# Control.net
KiCad netlist of a schematic drawn in Altium Designer
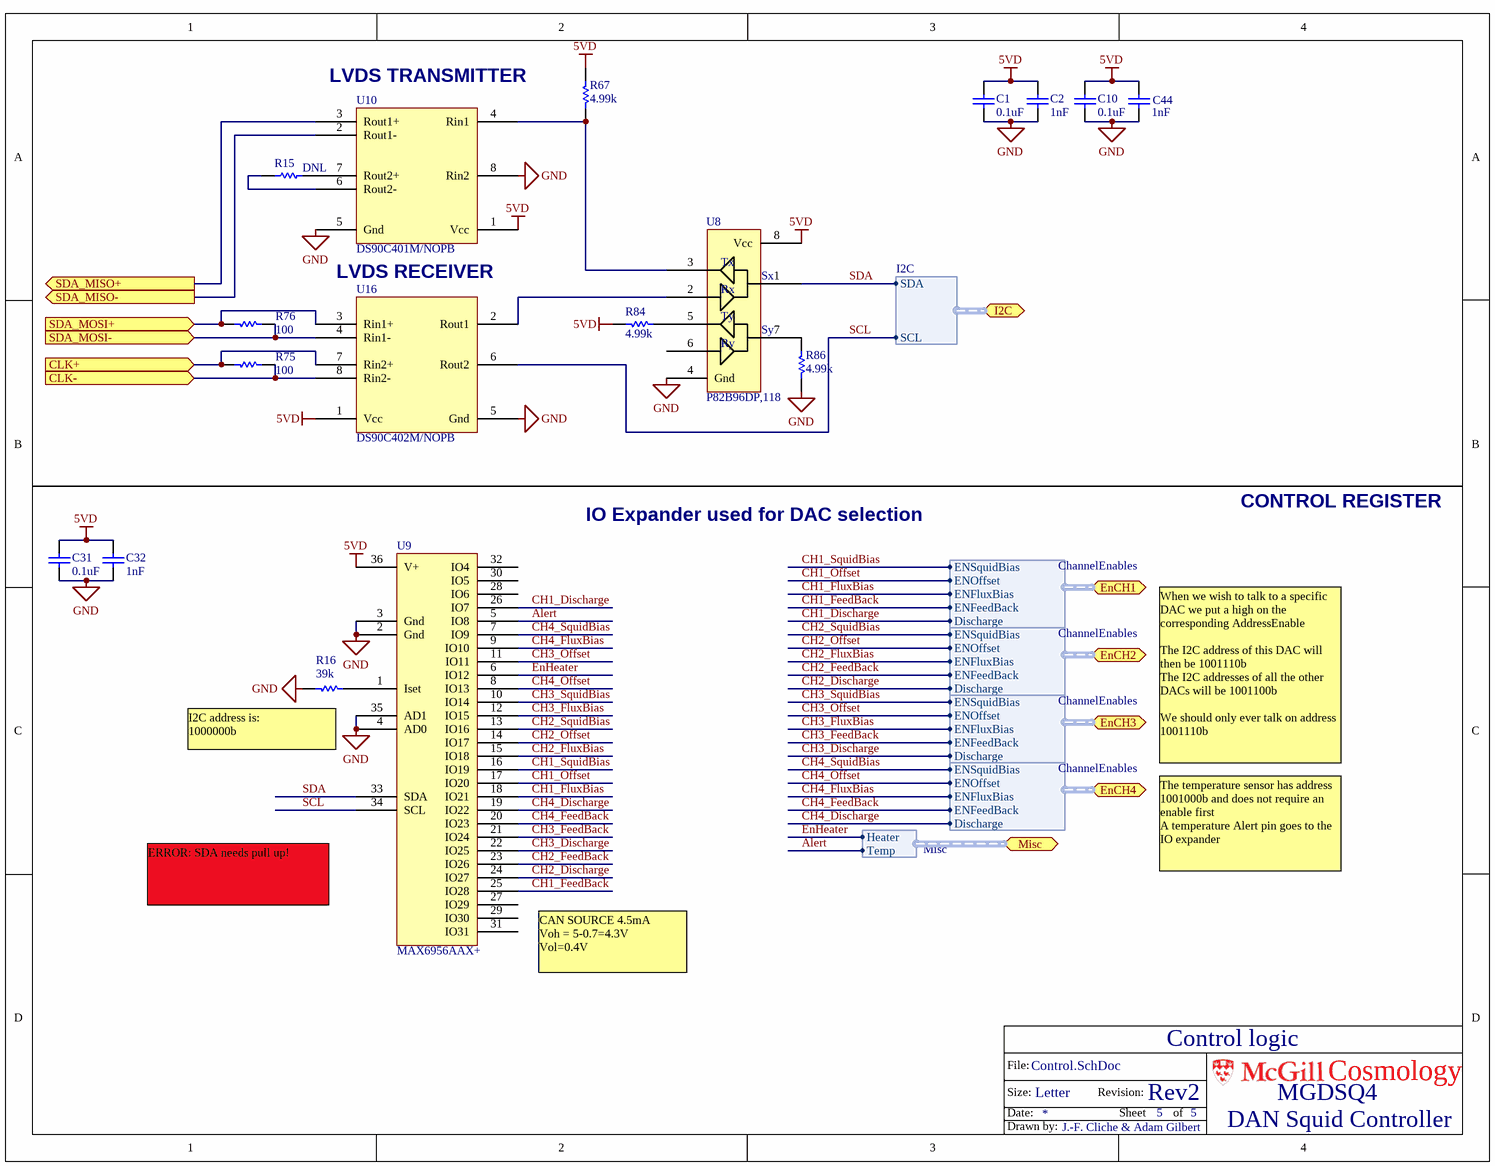
[diagram p0: Control.SchDoc]

(export (version "E")
  (design (tool "Eeschema 10.0.6"))
  (components
    (comp (ref "C1")
      (value "0.1uF")
      (footprint "0603")
      (description "Capacitor, Ceramic, 0603")
      (fields (field (name "MANUFACTURER") "Generic"))
      (libsource (lib "MiniSquidCtrl") (part "Cap0603"))
    )
    (comp (ref "C2")
      (value "1nF")
      (footprint "0603")
      (description "Capacitor, Ceramic, 0603")
      (fields (field (name "MANUFACTURER") "Generic"))
      (libsource (lib "MiniSquidCtrl") (part "Cap0603"))
    )
    (comp (ref "C10")
      (value "0.1uF")
      (footprint "0603")
      (description "Capacitor, Ceramic, 0603")
      (fields (field (name "MANUFACTURER") "Generic"))
      (libsource (lib "MiniSquidCtrl") (part "Cap0603"))
    )
    (comp (ref "C31")
      (value "0.1uF")
      (footprint "0603")
      (description "Capacitor, Ceramic, 0603")
      (fields (field (name "MANUFACTURER") "Generic"))
      (libsource (lib "MiniSquidCtrl") (part "Cap0603"))
    )
    (comp (ref "C32")
      (value "1nF")
      (footprint "0603")
      (description "Capacitor, Ceramic, 0603")
      (fields (field (name "MANUFACTURER") "Generic"))
      (libsource (lib "MiniSquidCtrl") (part "Cap0603"))
    )
    (comp (ref "C44")
      (value "1nF")
      (footprint "0603")
      (description "Capacitor, Ceramic, 0603")
      (fields (field (name "MANUFACTURER") "Generic"))
      (libsource (lib "MiniSquidCtrl") (part "Cap0603"))
    )
    (comp (ref "R15")
      (value "DNL")
      (footprint "0603")
      (description "RES 0603")
      (fields (field (name "MANUFACTURER") "Generic"))
      (libsource (lib "MiniSquidCtrl") (part "Res0603"))
    )
    (comp (ref "R16")
      (value "39k")
      (description "RES 0603")
      (fields (field (name "MANUFACTURER") "Generic") (field (name "TOLERANCE") "±1%"))
      (libsource (lib "MiniSquidCtrl") (part "RES 0603"))
    )
    (comp (ref "R67")
      (value "4.99k")
      (footprint "0603")
      (description "RES 0603")
      (fields (field (name "MANUFACTURER") "Generic"))
      (libsource (lib "MiniSquidCtrl") (part "Res0603"))
    )
    (comp (ref "R75")
      (value "100")
      (footprint "0603")
      (description "RES 0603")
      (fields (field (name "MANUFACTURER") "Generic"))
      (libsource (lib "MiniSquidCtrl") (part "RES 0603"))
    )
    (comp (ref "R76")
      (value "100")
      (footprint "0603")
      (description "RES 0603")
      (fields (field (name "MANUFACTURER") "Generic"))
      (libsource (lib "MiniSquidCtrl") (part "RES 0603"))
    )
    (comp (ref "R84")
      (value "4.99k")
      (footprint "0603")
      (description "RES 0603")
      (fields (field (name "MANUFACTURER") "Generic"))
      (libsource (lib "MiniSquidCtrl") (part "Res0603"))
    )
    (comp (ref "R86")
      (value "4.99k")
      (footprint "0603")
      (description "RES 0603")
      (fields (field (name "MANUFACTURER") "Generic"))
      (libsource (lib "MiniSquidCtrl") (part "Res0603"))
    )
    (comp (ref "U8")
      (value "P82B96DP,118")
      (footprint "MSOP8-P82B96")
      (description "IC DUAL BI-DIR BUS BUFFER 8-TSSOP")
      (libsource (lib "MiniSquidCtrl") (part "P82B96"))
    )
    (comp (ref "U9")
      (value "MAX6956AAX+")
      (footprint "SOP36Body15.4mmx7.5mm")
      (description "IO expander 28 IOs, I2C")
      (libsource (lib "MiniSquidCtrl") (part "MAX6956AAX+"))
    )
    (comp (ref "U10")
      (value "DS90C401M/NOPB")
      (footprint "SO8")
      (description "IC DRV LVDS DUAL DIFF SGNL 8SOIC")
      (libsource (lib "MiniSquidCtrl") (part "DS90C401M/NOPB"))
    )
    (comp (ref "U16")
      (value "DS90C402M/NOPB")
      (footprint "SO8")
      (description "IC REC LVDS DUAL DIFF SGNL 8SOIC")
      (libsource (lib "MiniSquidCtrl") (part "DS90C402M/NOPB"))
    )
  )
  (nets
    (net (code "4") (name "/Alert") (class "Default")
      (node (ref "U9") (pin "5") (pinfunction "IO8_5") (pintype "passive"))
    )
    (net (code "5") (name "/CH1_Discharge") (class "Default")
      (node (ref "U9") (pin "26") (pinfunction "IO7_26") (pintype "passive"))
    )
    (net (code "6") (name "/CH1_FeedBack") (class "Default")
      (node (ref "U9") (pin "25") (pinfunction "IO28_25") (pintype "passive"))
    )
    (net (code "7") (name "/CH1_FluxBias") (class "Default")
      (node (ref "U9") (pin "18") (pinfunction "IO21_18") (pintype "passive"))
    )
    (net (code "8") (name "/CH1_Offset") (class "Default")
      (node (ref "U9") (pin "17") (pinfunction "IO20_17") (pintype "passive"))
    )
    (net (code "9") (name "/CH1_SquidBias") (class "Default")
      (node (ref "U9") (pin "16") (pinfunction "IO19_16") (pintype "passive"))
    )
    (net (code "10") (name "/CH2_Discharge") (class "Default")
      (node (ref "U9") (pin "24") (pinfunction "IO27_24") (pintype "passive"))
    )
    (net (code "11") (name "/CH2_FeedBack") (class "Default")
      (node (ref "U9") (pin "23") (pinfunction "IO26_23") (pintype "passive"))
    )
    (net (code "12") (name "/CH2_FluxBias") (class "Default")
      (node (ref "U9") (pin "15") (pinfunction "IO18_15") (pintype "passive"))
    )
    (net (code "13") (name "/CH2_Offset") (class "Default")
      (node (ref "U9") (pin "14") (pinfunction "IO17_14") (pintype "passive"))
    )
    (net (code "14") (name "/CH2_SquidBias") (class "Default")
      (node (ref "U9") (pin "13") (pinfunction "IO16_13") (pintype "passive"))
    )
    (net (code "15") (name "/CH3_Discharge") (class "Default")
      (node (ref "U9") (pin "22") (pinfunction "IO25_22") (pintype "passive"))
    )
    (net (code "16") (name "/CH3_FeedBack") (class "Default")
      (node (ref "U9") (pin "21") (pinfunction "IO24_21") (pintype "passive"))
    )
    (net (code "17") (name "/CH3_FluxBias") (class "Default")
      (node (ref "U9") (pin "12") (pinfunction "IO15_12") (pintype "passive"))
    )
    (net (code "18") (name "/CH3_Offset") (class "Default")
      (node (ref "U9") (pin "11") (pinfunction "IO11_11") (pintype "passive"))
    )
    (net (code "19") (name "/CH3_SquidBias") (class "Default")
      (node (ref "U9") (pin "10") (pinfunction "IO14_10") (pintype "passive"))
    )
    (net (code "20") (name "/CH4_Discharge") (class "Default")
      (node (ref "U9") (pin "19") (pinfunction "IO22_19") (pintype "passive"))
    )
    (net (code "21") (name "/CH4_FeedBack") (class "Default")
      (node (ref "U9") (pin "20") (pinfunction "IO23_20") (pintype "passive"))
    )
    (net (code "22") (name "/CH4_FluxBias") (class "Default")
      (node (ref "U9") (pin "9") (pinfunction "IO10_9") (pintype "passive"))
    )
    (net (code "23") (name "/CH4_Offset") (class "Default")
      (node (ref "U9") (pin "8") (pinfunction "IO13_8") (pintype "passive"))
    )
    (net (code "24") (name "/CH4_SquidBias") (class "Default")
      (node (ref "U9") (pin "7") (pinfunction "IO9_7") (pintype "passive"))
    )
    (net (code "25") (name "/CLK+") (class "Default")
      (node (ref "R75") (pin "2") (pinfunction "2_2") (pintype "passive"))
      (node (ref "U16") (pin "7") (pinfunction "Rin2+_7") (pintype "passive"))
    )
    (net (code "26") (name "/CLK-") (class "Default")
      (node (ref "R75") (pin "1") (pinfunction "1_1") (pintype "passive"))
      (node (ref "U16") (pin "8") (pinfunction "Rin2-_8") (pintype "passive"))
    )
    (net (code "27") (name "/EnHeater") (class "Default")
      (node (ref "U9") (pin "6") (pinfunction "IO12_6") (pintype "passive"))
    )
    (net (code "28") (name "/SCL") (class "Default")
      (node (ref "U16") (pin "6") (pinfunction "Rout2_6") (pintype "passive"))
      (node (ref "U9") (pin "34") (pinfunction "SCL_34") (pintype "passive"))
    )
    (net (code "29") (name "/SDA") (class "Default")
      (node (ref "U8") (pin "1") (pinfunction "Sx_1") (pintype "passive"))
      (node (ref "U9") (pin "33") (pinfunction "SDA_33") (pintype "passive"))
    )
    (net (code "30") (name "/SDA_MISO+") (class "Default")
      (node (ref "U10") (pin "3") (pinfunction "Rout1+_3") (pintype "passive"))
    )
    (net (code "31") (name "/SDA_MISO-") (class "Default")
      (node (ref "U10") (pin "2") (pinfunction "Rout1-_2") (pintype "passive"))
    )
    (net (code "32") (name "/SDA_MOSI+") (class "Default")
      (node (ref "R76") (pin "2") (pinfunction "2_2") (pintype "passive"))
      (node (ref "U16") (pin "3") (pinfunction "Rin1+_3") (pintype "passive"))
    )
    (net (code "33") (name "/SDA_MOSI-") (class "Default")
      (node (ref "R76") (pin "1") (pinfunction "1_1") (pintype "passive"))
      (node (ref "U16") (pin "4") (pinfunction "Rin1-_4") (pintype "passive"))
    )
    (net (code "37") (name "5VD") (class "Default")
      (node (ref "C1") (pin "2") (pinfunction "2_2") (pintype "passive"))
      (node (ref "C10") (pin "2") (pinfunction "2_2") (pintype "passive"))
      (node (ref "C2") (pin "2") (pinfunction "2_2") (pintype "passive"))
      (node (ref "C31") (pin "2") (pinfunction "2_2") (pintype "passive"))
      (node (ref "C32") (pin "2") (pinfunction "2_2") (pintype "passive"))
      (node (ref "C44") (pin "2") (pinfunction "2_2") (pintype "passive"))
      (node (ref "R67") (pin "2") (pinfunction "2_2") (pintype "passive"))
      (node (ref "R84") (pin "2") (pinfunction "2_2") (pintype "passive"))
      (node (ref "U10") (pin "1") (pinfunction "Vcc_1") (pintype "passive"))
      (node (ref "U16") (pin "1") (pinfunction "Vcc_1") (pintype "passive"))
      (node (ref "U8") (pin "8") (pinfunction "Vcc_8") (pintype "passive"))
      (node (ref "U9") (pin "36") (pinfunction "V+_36") (pintype "passive"))
    )
    (net (code "38") (name "GND") (class "Default")
      (node (ref "C1") (pin "1") (pinfunction "1_1") (pintype "passive"))
      (node (ref "C10") (pin "1") (pinfunction "1_1") (pintype "passive"))
      (node (ref "C2") (pin "1") (pinfunction "1_1") (pintype "passive"))
      (node (ref "C31") (pin "1") (pinfunction "1_1") (pintype "passive"))
      (node (ref "C32") (pin "1") (pinfunction "1_1") (pintype "passive"))
      (node (ref "C44") (pin "1") (pinfunction "1_1") (pintype "passive"))
      (node (ref "R16") (pin "2") (pinfunction "2_2") (pintype "passive"))
      (node (ref "R86") (pin "1") (pinfunction "1_1") (pintype "passive"))
      (node (ref "U10") (pin "5") (pinfunction "Gnd_5") (pintype "passive"))
      (node (ref "U10") (pin "8") (pinfunction "Rin2_8") (pintype "passive"))
      (node (ref "U16") (pin "5") (pinfunction "Gnd_5") (pintype "passive"))
      (node (ref "U8") (pin "4") (pinfunction "Gnd_4") (pintype "passive"))
      (node (ref "U9") (pin "2") (pinfunction "Gnd_2") (pintype "passive"))
      (node (ref "U9") (pin "3") (pinfunction "Gnd_3") (pintype "passive"))
      (node (ref "U9") (pin "35") (pinfunction "AD1_35") (pintype "passive"))
      (node (ref "U9") (pin "4") (pinfunction "AD0_4") (pintype "passive"))
    )
    (net (code "39") (name "Net-(U8-Sy)") (class "Default")
      (node (ref "R86") (pin "2") (pinfunction "2_2") (pintype "passive"))
      (node (ref "U8") (pin "7") (pinfunction "Sy_7") (pintype "passive"))
    )
    (net (code "40") (name "Net-(U8-Ty)") (class "Default")
      (node (ref "R84") (pin "1") (pinfunction "1_1") (pintype "passive"))
      (node (ref "U8") (pin "5") (pinfunction "Ty_5") (pintype "passive"))
    )
    (net (code "41") (name "Net-(U9-Iset)") (class "Default")
      (node (ref "R16") (pin "1") (pinfunction "1_1") (pintype "passive"))
      (node (ref "U9") (pin "1") (pinfunction "Iset_1") (pintype "passive"))
    )
    (net (code "42") (name "Net-(U10-Rin1)") (class "Default")
      (node (ref "R67") (pin "1") (pinfunction "1_1") (pintype "passive"))
      (node (ref "U10") (pin "4") (pinfunction "Rin1_4") (pintype "passive"))
      (node (ref "U8") (pin "3") (pinfunction "Tx_3") (pintype "passive"))
    )
    (net (code "43") (name "Net-(U10-Rout2+)") (class "Default")
      (node (ref "R15") (pin "2") (pinfunction "2_2") (pintype "passive"))
      (node (ref "U10") (pin "7") (pinfunction "Rout2+_7") (pintype "passive"))
    )
    (net (code "44") (name "Net-(U10-Rout2-)") (class "Default")
      (node (ref "R15") (pin "1") (pinfunction "1_1") (pintype "passive"))
      (node (ref "U10") (pin "6") (pinfunction "Rout2-_6") (pintype "passive"))
    )
    (net (code "45") (name "Net-(U16-Rout1)") (class "Default")
      (node (ref "U16") (pin "2") (pinfunction "Rout1_2") (pintype "passive"))
      (node (ref "U8") (pin "2") (pinfunction "Rx_2") (pintype "passive"))
    )
    (net (code "46") (name "unconnected-(U8-Ry-Pad6)") (class "Default")
      (node (ref "U8") (pin "6") (pinfunction "Ry_6") (pintype "passive"))
    )
    (net (code "47") (name "unconnected-(U9-IO4-Pad32)") (class "Default")
      (node (ref "U9") (pin "32") (pinfunction "IO4_32") (pintype "passive"))
    )
    (net (code "48") (name "unconnected-(U9-IO5-Pad30)") (class "Default")
      (node (ref "U9") (pin "30") (pinfunction "IO5_30") (pintype "passive"))
    )
    (net (code "49") (name "unconnected-(U9-IO6-Pad28)") (class "Default")
      (node (ref "U9") (pin "28") (pinfunction "IO6_28") (pintype "passive"))
    )
    (net (code "50") (name "unconnected-(U9-IO29-Pad27)") (class "Default")
      (node (ref "U9") (pin "27") (pinfunction "IO29_27") (pintype "passive"))
    )
    (net (code "51") (name "unconnected-(U9-IO30-Pad29)") (class "Default")
      (node (ref "U9") (pin "29") (pinfunction "IO30_29") (pintype "passive"))
    )
    (net (code "52") (name "unconnected-(U9-IO31-Pad31)") (class "Default")
      (node (ref "U9") (pin "31") (pinfunction "IO31_31") (pintype "passive"))
    )
  )
)
